# Sheet3.net
KiCad netlist of a schematic drawn in Altium Designer
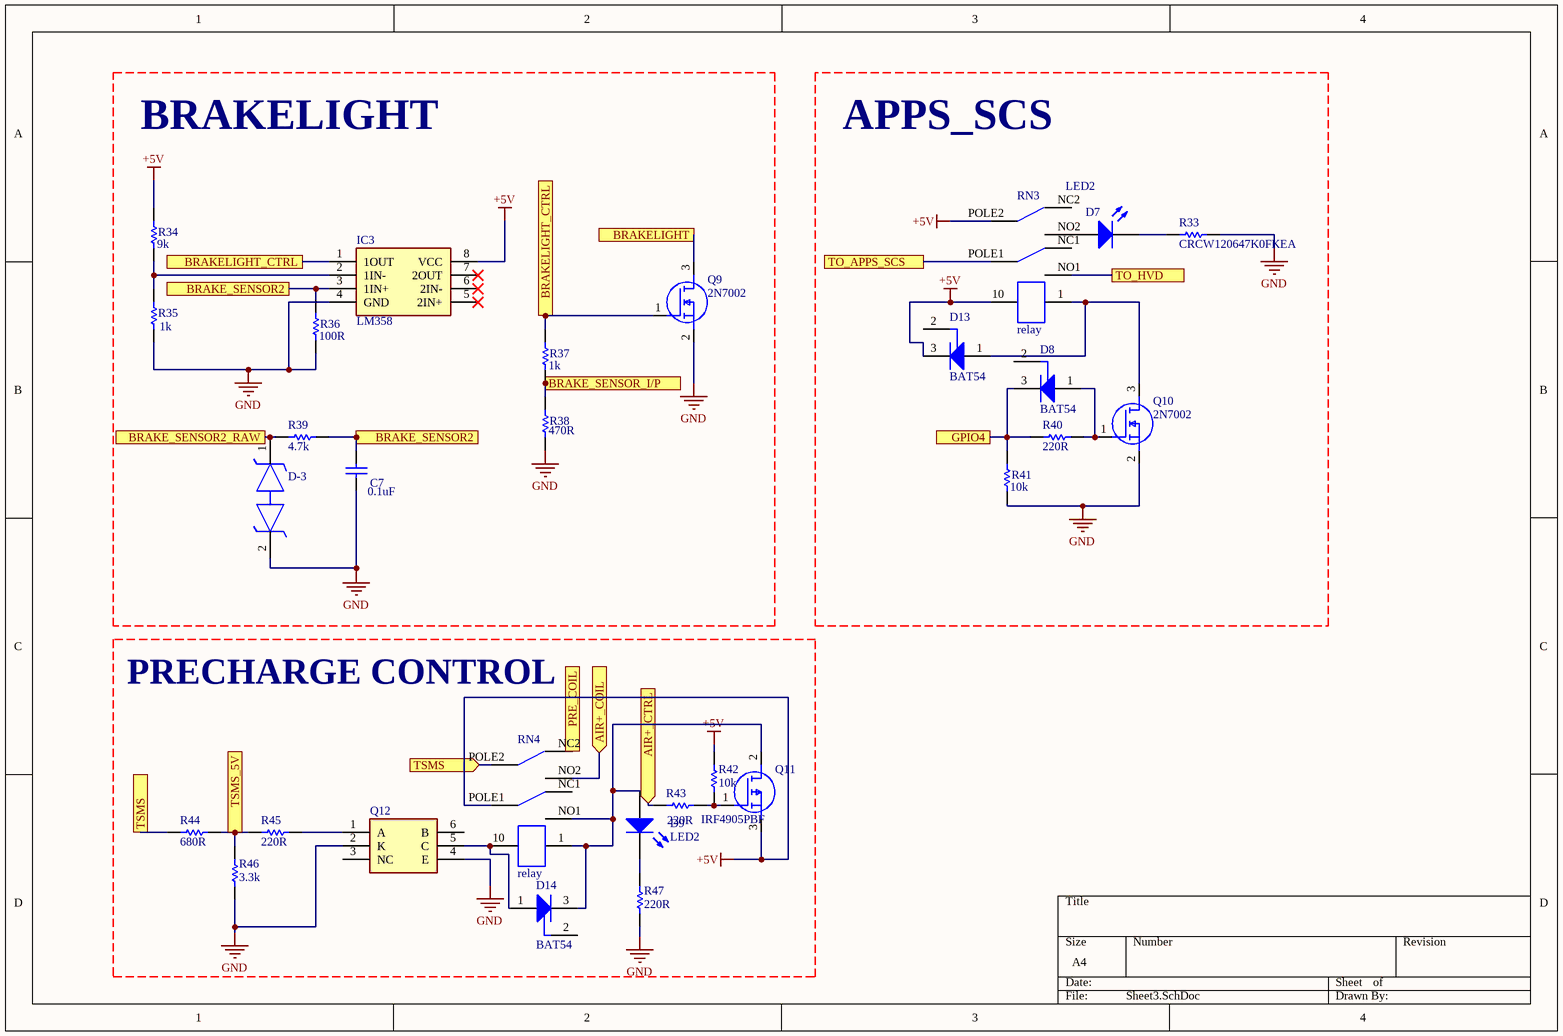
[diagram p0: Sheet3.SchDoc]

(export (version "E")
  (design (tool "Eeschema 10.0.6"))
  (components
    (comp (ref "C7")
      (value "0.1uF")
      (footprint "KEMT-1206-2_N")
      (description "CAP, Ceramic, 0.1 uF, +/- 10%, 50 V, -55 to 125 degC, 1206 (3216 Metric), RoHS, Tape and Reel")
      (fields (field (name "MANUFACTURER") "Kemet"))
      (libsource (lib "TSAL LV Schlib") (part "CAPACITOR"))
    )
    (comp (ref "D-3")
      (value "TPD1E6B06DPLR")
      (footprint "R1206")
      (libsource (lib "Diode_Texas_Instruments_TPD1E6B06DPLR_eec") (part "TPD1E6B06DPLR"))
    )
    (comp (ref "D7")
      (value "LED2")
      (footprint "3.2X1.6X1.1")
      (description "Typical RED, GREEN, YELLOW, AMBER GaAs LED")
      (fields (field (name "PUBLISHER") "Altium Limited"))
      (libsource (lib "Miscellaneous Devices") (part "LED2"))
    )
    (comp (ref "D8")
      (value "BAT54")
      (footprint "INF-SOT23_N")
      (description "Silicon Schottky Diode, SOT23, Reel, Green")
      (fields (field (name "MANUFACTURER") "Infineon"))
      (libsource (lib "Schlib1") (part "CMP-1182-00010-1"))
    )
    (comp (ref "D9")
      (value "LED2")
      (footprint "3.2X1.6X1.1")
      (description "Typical RED, GREEN, YELLOW, AMBER GaAs LED")
      (fields (field (name "PUBLISHER") "Altium Limited"))
      (libsource (lib "Miscellaneous Devices") (part "LED2"))
    )
    (comp (ref "D13")
      (value "BAT54")
      (footprint "INF-SOT23_N")
      (description "Silicon Schottky Diode, SOT23, Reel, Green")
      (fields (field (name "MANUFACTURER") "Infineon"))
      (libsource (lib "Schlib1") (part "CMP-1182-00010-1"))
    )
    (comp (ref "D14")
      (value "BAT54")
      (footprint "INF-SOT23_N")
      (description "Silicon Schottky Diode, SOT23, Reel, Green")
      (fields (field (name "MANUFACTURER") "Infineon"))
      (libsource (lib "Schlib1") (part "CMP-1182-00010-1"))
    )
    (comp (ref "IC3")
      (value "LM358")
      (footprint "SamacSys:SOP100P600X150-8N")
      (description "Integrated Circuit")
      (libsource (lib "*") (part "LM358"))
    )
    (comp (ref "Q9")
      (value "2N7002")
      (footprint "SamacSys:SOT96P240X120-3N")
      (description "MOSFET (N-Channel)")
      (fields (field (name "MOUSER PART NUMBER") "781-2N7002"))
      (libsource (lib "*") (part "2N7002"))
    )
    (comp (ref "Q10")
      (value "2N7002")
      (footprint "SamacSys:SOT96P240X120-3N")
      (description "MOSFET (N-Channel)")
      (fields (field (name "MOUSER PART NUMBER") "781-2N7002"))
      (libsource (lib "*") (part "2N7002"))
    )
    (comp (ref "Q11")
      (value "IRF4905PBF")
      (footprint "SamacSys:TO254P469X1042X1967-3P")
      (description "MOSFET (P-Channel)")
      (fields (field (name "MOUSER PART NUMBER") "942-IRF4905PBF"))
      (libsource (lib "*") (part "IRF4905PBF"))
    )
    (comp (ref "Q12")
      (value "MCT2ESM")
      (footprint "SamacSys:SOT254P916X480-6N")
      (description "Phototransistor")
      (fields (field (name "MOUSER PART NUMBER") "512-MCT2ESM"))
      (libsource (lib "*") (part "MCT2ESM"))
    )
    (comp (ref "R33")
      (value "CRCW120647K0FKEA")
      (footprint "RESC3216X60X45NL10T20 - duplicate")
      (fields (field (name "MANUFACTURER") "Vishay Dale"))
      (libsource (lib "Schlib1") (part "CMP-2003-02213-1"))
    )
    (comp (ref "R34")
      (value "9k")
      (footprint "RESC3216X60X45NL10T20 - duplicate")
      (fields (field (name "PART NUMBER") "CRCW120647K0FKEA") (field (name "MANUFACTURER") "Vishay Dale"))
      (libsource (lib "Schlib1") (part "CMP-2003-02213-1"))
    )
    (comp (ref "R35")
      (value "1k")
      (footprint "RESC3216X60X45NL10T20 - duplicate")
      (fields (field (name "PART NUMBER") "CRCW120647K0FKEA") (field (name "MANUFACTURER") "Vishay Dale"))
      (libsource (lib "Schlib1") (part "CMP-2003-02213-1"))
    )
    (comp (ref "R36")
      (value "100R")
      (footprint "RESC3216X60X45NL10T20 - duplicate")
      (fields (field (name "PART NUMBER") "CRCW120647K0FKEA") (field (name "MANUFACTURER") "Vishay Dale"))
      (libsource (lib "Schlib1") (part "CMP-2003-02213-1"))
    )
    (comp (ref "R37")
      (value "1k")
      (footprint "RESC3216X60X45NL10T20 - duplicate")
      (fields (field (name "PART NUMBER") "CRCW120647K0FKEA") (field (name "MANUFACTURER") "Vishay Dale"))
      (libsource (lib "Schlib1") (part "CMP-2003-02213-1"))
    )
    (comp (ref "R38")
      (value "470R")
      (footprint "RESC3216X60X45NL10T20 - duplicate")
      (fields (field (name "PART NUMBER") "CRCW120647K0FKEA") (field (name "MANUFACTURER") "Vishay Dale"))
      (libsource (lib "Schlib1") (part "CMP-2003-02213-1"))
    )
    (comp (ref "R39")
      (value "4.7k")
      (footprint "RESC3216X60X45NL10T20 - duplicate")
      (fields (field (name "PART NUMBER") "CRCW120647K0FKEA") (field (name "MANUFACTURER") "Vishay Dale"))
      (libsource (lib "Schlib1") (part "CMP-2003-02213-1"))
    )
    (comp (ref "R40")
      (value "220R")
      (footprint "RESC3216X60X45NL10T20 - duplicate")
      (fields (field (name "PART NUMBER") "CRCW120647K0FKEA") (field (name "MANUFACTURER") "Vishay Dale"))
      (libsource (lib "Schlib1") (part "CMP-2003-02213-1"))
    )
    (comp (ref "R41")
      (value "10k")
      (footprint "RESC3216X60X45NL10T20 - duplicate")
      (fields (field (name "PART NUMBER") "CRCW120647K0FKEA") (field (name "MANUFACTURER") "Vishay Dale"))
      (libsource (lib "Schlib1") (part "CMP-2003-02213-1"))
    )
    (comp (ref "R42")
      (value "10k")
      (footprint "R1206")
      (fields (field (name "PART NUMBER") "CRCW120647K0FKEA") (field (name "MANUFACTURER") "Vishay Dale"))
      (libsource (lib "Schlib1") (part "RES"))
    )
    (comp (ref "R43")
      (value "220R")
      (footprint "R1206")
      (fields (field (name "PART NUMBER") "CRCW120647K0FKEA") (field (name "MANUFACTURER") "Vishay Dale"))
      (libsource (lib "Schlib1") (part "RES"))
    )
    (comp (ref "R44")
      (value "680R")
      (footprint "RESC3216X60X45NL10T20 - duplicate")
      (fields (field (name "PART NUMBER") "CRCW120647K0FKEA") (field (name "MANUFACTURER") "Vishay Dale"))
      (libsource (lib "Schlib1") (part "CMP-2003-02213-1"))
    )
    (comp (ref "R45")
      (value "220R")
      (footprint "R1206")
      (fields (field (name "PART NUMBER") "CRCW120647K0FKEA") (field (name "MANUFACTURER") "Vishay Dale"))
      (libsource (lib "Schlib1") (part "RES"))
    )
    (comp (ref "R46")
      (value "3.3k")
      (footprint "RESC3216X60X45NL10T20 - duplicate")
      (fields (field (name "PART NUMBER") "CRCW120647K0FKEA") (field (name "MANUFACTURER") "Vishay Dale"))
      (libsource (lib "Schlib1") (part "CMP-2003-02213-1"))
    )
    (comp (ref "R47")
      (value "220R")
      (footprint "R1206")
      (fields (field (name "PART NUMBER") "CRCW120647K0FKEA") (field (name "MANUFACTURER") "Vishay Dale"))
      (libsource (lib "Schlib1") (part "RES"))
    )
    (comp (ref "RN3") (value "relay") (footprint "relaytq") (libsource (lib "Schlib1") (part "relay")))
    (comp (ref "RN4") (value "relay") (footprint "relaytq") (libsource (lib "Schlib1") (part "relay")))
  )
  (nets
    (net (code "1") (name "+5V") (class "Default")
      (node (ref "D13") (pin "3") (pinfunction "K_3") (pintype "passive"))
      (node (ref "IC3") (pin "8") (pinfunction "VCC_8") (pintype "passive"))
      (node (ref "Q11") (pin "3") (pinfunction "S_3") (pintype "passive"))
      (node (ref "R34") (pin "2") (pinfunction "2_2") (pintype "passive"))
      (node (ref "R42") (pin "2") (pinfunction "2_2") (pintype "passive"))
      (node (ref "RN3") (pin "10") (pinfunction "10_10") (pintype "passive"))
      (node (ref "RN3") (pin "POLE2") (pinfunction "POLE2_POLE2") (pintype "passive"))
      (node (ref "RN4") (pin "POLE1") (pinfunction "POLE1_POLE1") (pintype "passive"))
    )
    (net (code "2") (name "/AIR+_COIL") (class "Default")
      (node (ref "RN4") (pin "NO2") (pinfunction "NO2_NO2") (pintype "passive"))
    )
    (net (code "3") (name "/AIR+_CTRL") (class "Default")
      (node (ref "R43") (pin "1") (pinfunction "1_1") (pintype "passive"))
    )
    (net (code "4") (name "/BRAKELIGHT") (class "Default")
      (node (ref "Q9") (pin "3") (pinfunction "D_3") (pintype "passive"))
    )
    (net (code "5") (name "/BRAKELIGHT_CTRL") (class "Default")
      (node (ref "IC3") (pin "1") (pinfunction "1OUT_1") (pintype "passive"))
      (node (ref "Q9") (pin "1") (pinfunction "G_1") (pintype "passive"))
      (node (ref "R37") (pin "2") (pinfunction "2_2") (pintype "passive"))
    )
    (net (code "6") (name "/BRAKE_SENSOR2") (class "Default")
      (node (ref "C7") (pin "2") (pinfunction "2_2") (pintype "passive"))
      (node (ref "IC3") (pin "3") (pinfunction "1IN+_3") (pintype "passive"))
      (node (ref "R36") (pin "2") (pinfunction "2_2") (pintype "passive"))
      (node (ref "R39") (pin "1") (pinfunction "1_1") (pintype "passive"))
    )
    (net (code "7") (name "/BRAKE_SENSOR2_RAW") (class "Default")
      (node (ref "D-3") (pin "1") (pinfunction "1_1") (pintype "passive"))
      (node (ref "R39") (pin "2") (pinfunction "2_2") (pintype "passive"))
    )
    (net (code "8") (name "/BRAKE_SENSOR_I{slash}P") (class "Default")
      (node (ref "R37") (pin "1") (pinfunction "1_1") (pintype "passive"))
      (node (ref "R38") (pin "2") (pinfunction "2_2") (pintype "passive"))
    )
    (net (code "9") (name "/GPIO4") (class "Default")
      (node (ref "D8") (pin "3") (pinfunction "K_3") (pintype "passive"))
      (node (ref "R40") (pin "2") (pinfunction "2_2") (pintype "passive"))
      (node (ref "R41") (pin "2") (pinfunction "2_2") (pintype "passive"))
    )
    (net (code "10") (name "/PRE_COIL") (class "Default")
      (node (ref "RN4") (pin "NC2") (pinfunction "NC2_NC2") (pintype "passive"))
    )
    (net (code "11") (name "/TO_APPS_SCS") (class "Default")
      (node (ref "RN3") (pin "POLE1") (pinfunction "POLE1_POLE1") (pintype "passive"))
    )
    (net (code "12") (name "/TO_HVD") (class "Default")
      (node (ref "RN3") (pin "NO1") (pinfunction "NO1_NO1") (pintype "passive"))
    )
    (net (code "13") (name "/TSMS") (class "Default")
      (node (ref "R44") (pin "2") (pinfunction "2_2") (pintype "passive"))
      (node (ref "RN4") (pin "POLE2") (pinfunction "POLE2_POLE2") (pintype "passive"))
    )
    (net (code "14") (name "/TSMS_5V") (class "Default")
      (node (ref "R44") (pin "1") (pinfunction "1_1") (pintype "passive"))
      (node (ref "R45") (pin "2") (pinfunction "2_2") (pintype "passive"))
      (node (ref "R46") (pin "2") (pinfunction "2_2") (pintype "passive"))
    )
    (net (code "15") (name "GND") (class "Default")
      (node (ref "C7") (pin "1") (pinfunction "1_1") (pintype "passive"))
      (node (ref "D-3") (pin "2") (pinfunction "2_2") (pintype "passive"))
      (node (ref "IC3") (pin "4") (pinfunction "GND_4") (pintype "passive"))
      (node (ref "Q10") (pin "2") (pinfunction "S_2") (pintype "passive"))
      (node (ref "Q12") (pin "2") (pinfunction "K_2") (pintype "passive"))
      (node (ref "Q12") (pin "4") (pinfunction "E_4") (pintype "passive"))
      (node (ref "Q9") (pin "2") (pinfunction "S_2") (pintype "passive"))
      (node (ref "R33") (pin "1") (pinfunction "1_1") (pintype "passive"))
      (node (ref "R35") (pin "1") (pinfunction "1_1") (pintype "passive"))
      (node (ref "R36") (pin "1") (pinfunction "1_1") (pintype "passive"))
      (node (ref "R38") (pin "1") (pinfunction "1_1") (pintype "passive"))
      (node (ref "R41") (pin "1") (pinfunction "1_1") (pintype "passive"))
      (node (ref "R46") (pin "1") (pinfunction "1_1") (pintype "passive"))
      (node (ref "R47") (pin "2") (pinfunction "2_2") (pintype "passive"))
    )
    (net (code "16") (name "Net-(D7-A)") (class "Default")
      (node (ref "D7") (pin "1") (pinfunction "A_1") (pintype "passive"))
      (node (ref "RN3") (pin "NO2") (pinfunction "NO2_NO2") (pintype "passive"))
    )
    (net (code "17") (name "Net-(D7-K)") (class "Default")
      (node (ref "D7") (pin "2") (pinfunction "K_2") (pintype "passive"))
      (node (ref "R33") (pin "2") (pinfunction "2_2") (pintype "passive"))
    )
    (net (code "18") (name "Net-(D8-A)") (class "Default")
      (node (ref "D8") (pin "1") (pinfunction "A_1") (pintype "passive"))
      (node (ref "Q10") (pin "1") (pinfunction "G_1") (pintype "passive"))
      (node (ref "R40") (pin "1") (pinfunction "1_1") (pintype "passive"))
    )
    (net (code "19") (name "Net-(D9-K)") (class "Default")
      (node (ref "D9") (pin "2") (pinfunction "K_2") (pintype "passive"))
      (node (ref "R47") (pin "1") (pinfunction "1_1") (pintype "passive"))
    )
    (net (code "20") (name "Net-(D13-A)") (class "Default")
      (node (ref "D13") (pin "1") (pinfunction "A_1") (pintype "passive"))
      (node (ref "Q10") (pin "3") (pinfunction "D_3") (pintype "passive"))
      (node (ref "RN3") (pin "1") (pinfunction "1_1") (pintype "passive"))
    )
    (net (code "21") (name "Net-(D14-A)") (class "Default")
      (node (ref "D14") (pin "1") (pinfunction "A_1") (pintype "passive"))
      (node (ref "Q12") (pin "5") (pinfunction "C_5") (pintype "passive"))
      (node (ref "RN4") (pin "10") (pinfunction "10_10") (pintype "passive"))
    )
    (net (code "22") (name "Net-(D14-K)") (class "Default")
      (node (ref "D14") (pin "3") (pinfunction "K_3") (pintype "passive"))
      (node (ref "D9") (pin "1") (pinfunction "A_1") (pintype "passive"))
      (node (ref "Q11") (pin "2") (pinfunction "D_2") (pintype "passive"))
      (node (ref "RN4") (pin "1") (pinfunction "1_1") (pintype "passive"))
      (node (ref "RN4") (pin "NO1") (pinfunction "NO1_NO1") (pintype "passive"))
    )
    (net (code "23") (name "Net-(IC3-1IN-)") (class "Default")
      (node (ref "IC3") (pin "2") (pinfunction "1IN-_2") (pintype "passive"))
      (node (ref "R34") (pin "1") (pinfunction "1_1") (pintype "passive"))
      (node (ref "R35") (pin "2") (pinfunction "2_2") (pintype "passive"))
    )
    (net (code "24") (name "Net-(Q11-G)") (class "Default")
      (node (ref "Q11") (pin "1") (pinfunction "G_1") (pintype "passive"))
      (node (ref "R42") (pin "1") (pinfunction "1_1") (pintype "passive"))
      (node (ref "R43") (pin "2") (pinfunction "2_2") (pintype "passive"))
    )
    (net (code "25") (name "Net-(Q12-A)") (class "Default")
      (node (ref "Q12") (pin "1") (pinfunction "A_1") (pintype "passive"))
      (node (ref "R45") (pin "1") (pinfunction "1_1") (pintype "passive"))
    )
    (net (code "26") (name "unconnected-(D8-NC-Pad2)") (class "Default")
      (node (ref "D8") (pin "2") (pinfunction "NC_2") (pintype "passive"))
    )
    (net (code "27") (name "unconnected-(D13-NC-Pad2)") (class "Default")
      (node (ref "D13") (pin "2") (pinfunction "NC_2") (pintype "passive"))
    )
    (net (code "28") (name "unconnected-(D14-NC-Pad2)") (class "Default")
      (node (ref "D14") (pin "2") (pinfunction "NC_2") (pintype "passive"))
    )
    (net (code "29") (name "unconnected-(IC3-2IN+-Pad5)") (class "Default")
      (node (ref "IC3") (pin "5") (pinfunction "2IN+_5") (pintype "passive+no_connect"))
    )
    (net (code "30") (name "unconnected-(IC3-2IN--Pad6)") (class "Default")
      (node (ref "IC3") (pin "6") (pinfunction "2IN-_6") (pintype "passive+no_connect"))
    )
    (net (code "31") (name "unconnected-(IC3-2OUT-Pad7)") (class "Default")
      (node (ref "IC3") (pin "7") (pinfunction "2OUT_7") (pintype "passive+no_connect"))
    )
    (net (code "32") (name "unconnected-(Q12-B-Pad6)") (class "Default")
      (node (ref "Q12") (pin "6") (pinfunction "B_6") (pintype "passive"))
    )
    (net (code "33") (name "unconnected-(Q12-NC-Pad3)") (class "Default")
      (node (ref "Q12") (pin "3") (pinfunction "NC_3") (pintype "passive"))
    )
    (net (code "34") (name "unconnected-(RN3-PadNC1)") (class "Default")
      (node (ref "RN3") (pin "NC1") (pinfunction "NC1_NC1") (pintype "passive"))
    )
    (net (code "35") (name "unconnected-(RN3-PadNC2)") (class "Default")
      (node (ref "RN3") (pin "NC2") (pinfunction "NC2_NC2") (pintype "passive"))
    )
    (net (code "36") (name "unconnected-(RN4-PadNC1)") (class "Default")
      (node (ref "RN4") (pin "NC1") (pinfunction "NC1_NC1") (pintype "passive"))
    )
  )
)
